# M_Board_2011.net
KiCad netlist of a schematic drawn in Altium Designer
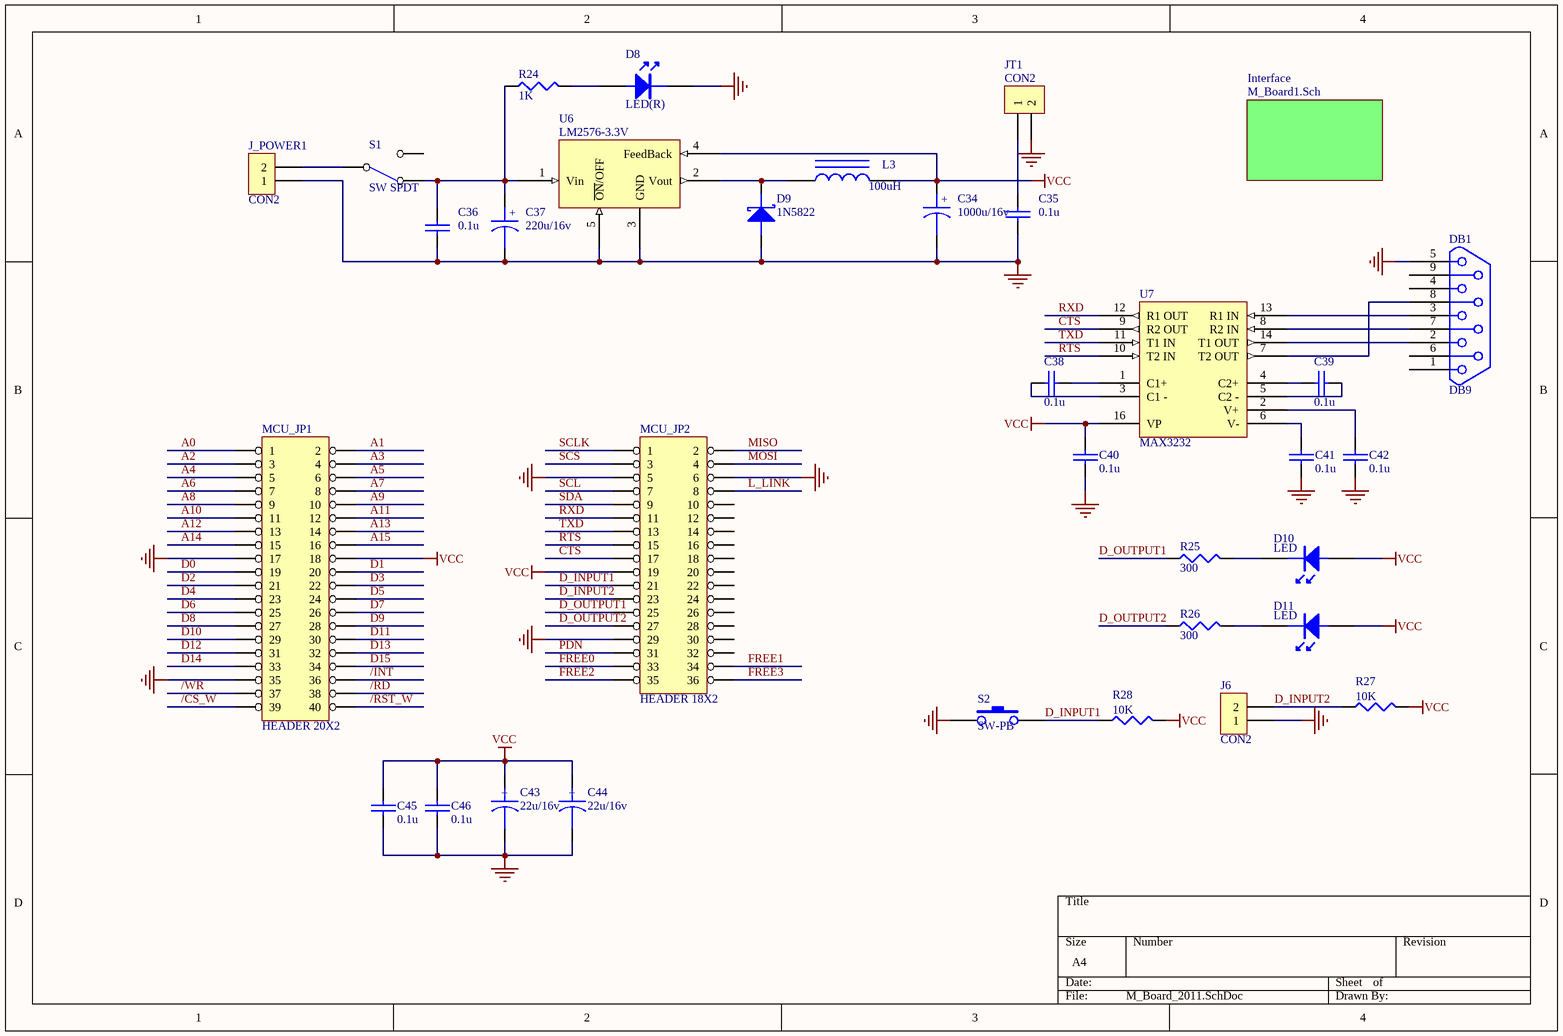
[diagram p0: M_Board_2011.SchDoc]

(export (version "E")
  (design (tool "Eeschema 10.0.6"))
  (components
    (comp (ref "C34")
      (value "1000u/16v")
      (footprint "RB.2/.4")
      (description "Capacitor")
      (libsource (lib "*") (part "CAPACITOR POL"))
    )
    (comp (ref "C35")
      (value "0.1u")
      (footprint "0603")
      (description "Capacitor")
      (libsource (lib "*") (part "CAP"))
    )
    (comp (ref "C36")
      (value "0.1u")
      (footprint "0603")
      (description "Capacitor")
      (libsource (lib "*") (part "CAP"))
    )
    (comp (ref "C37")
      (value "220u/16v")
      (footprint "RB.2/.4")
      (description "Capacitor")
      (libsource (lib "*") (part "CAPACITOR POL"))
    )
    (comp (ref "C38")
      (value "0.1u")
      (footprint "0603")
      (description "Capacitor")
      (libsource (lib "*") (part "CAP"))
    )
    (comp (ref "C39")
      (value "0.1u")
      (footprint "0603")
      (description "Capacitor")
      (libsource (lib "*") (part "CAP"))
    )
    (comp (ref "C40")
      (value "0.1u")
      (footprint "0603")
      (description "Capacitor")
      (libsource (lib "*") (part "CAP"))
    )
    (comp (ref "C41")
      (value "0.1u")
      (footprint "0603")
      (description "Capacitor")
      (libsource (lib "*") (part "CAP"))
    )
    (comp (ref "C42")
      (value "0.1u")
      (footprint "0603")
      (description "Capacitor")
      (libsource (lib "*") (part "CAP"))
    )
    (comp (ref "C43")
      (value "22u/16v")
      (footprint "RB.1/.2N")
      (description "Capacitor")
      (libsource (lib "") (part "CAPACITOR POL_1"))
    )
    (comp (ref "C44")
      (value "22u/16v")
      (footprint "RB.1/.2N")
      (description "Capacitor")
      (libsource (lib "") (part "CAPACITOR POL_1"))
    )
    (comp (ref "C45")
      (value "0.1u")
      (footprint "0603")
      (description "Capacitor")
      (libsource (lib "*") (part "CAP"))
    )
    (comp (ref "C46")
      (value "0.1u")
      (footprint "0603")
      (description "Capacitor")
      (libsource (lib "*") (part "CAP"))
    )
    (comp (ref "D8") (value "LED(R)") (footprint "LED2P") (libsource (lib "*") (part "LED")))
    (comp (ref "D9")
      (value "1N5822")
      (footprint "1005")
      (description "Schottky Diode")
      (libsource (lib "*") (part "DIODE SCHOTTKY"))
    )
    (comp (ref "D10") (value "LED") (footprint "LED2P") (libsource (lib "*") (part "LED")))
    (comp (ref "D11") (value "LED") (footprint "LED2P") (libsource (lib "*") (part "LED")))
    (comp (ref "DB1") (value "DB9") (footprint "DB9/F") (libsource (lib "*") (part "ICHIP3.S01_DB9_1")))
    (comp (ref "J6")
      (value "CON2")
      (footprint "SIP2")
      (description "Connector")
      (libsource (lib "*") (part "CON2"))
    )
    (comp (ref "JT1")
      (value "CON2")
      (footprint "SIP2")
      (description "Connector")
      (libsource (lib "") (part "CON2_1"))
    )
    (comp (ref "J_POWER1")
      (value "CON2")
      (footprint "PLUG")
      (description "Connector")
      (libsource (lib "*") (part "CON2"))
    )
    (comp (ref "L3") (value "100uH") (footprint "BED") (libsource (lib "*") (part "INDUCTOR IRON")))
    (comp (ref "MCU_JP1")
      (value "HEADER 20X2")
      (footprint "IDC40-2")
      (libsource (lib "*") (part "HEADER 20X2"))
    )
    (comp (ref "MCU_JP2")
      (value "HEADER 18X2")
      (footprint "IDC36-2")
      (libsource (lib "*") (part "HEADER 18X2"))
    )
    (comp (ref "R24") (value "1K") (footprint "0603") (libsource (lib "*") (part "RES1")))
    (comp (ref "R25") (value "300") (footprint "0603") (libsource (lib "*") (part "RES1")))
    (comp (ref "R26") (value "300") (footprint "0603") (libsource (lib "*") (part "RES1")))
    (comp (ref "R27") (value "10K") (footprint "0603") (libsource (lib "*") (part "RES1")))
    (comp (ref "R28") (value "10K") (footprint "0603") (libsource (lib "*") (part "RES1")))
    (comp (ref "S1") (value "SW SPDT") (footprint "SWITCH-3") (libsource (lib "*") (part "SW SPDT")))
    (comp (ref "S2") (value "SW-PB") (footprint "SW-4") (libsource (lib "*") (part "SW-PB")))
    (comp (ref "U6") (value "LM2576-3.3V") (footprint "DPAK-5") (libsource (lib "*") (part "LM2576")))
    (comp (ref "U7")
      (value "MAX3232")
      (footprint "SO-16")
      (description "+-15KV ESD-PROTECTED, +5V RS-232 TRANSCEIVERS")
      (libsource (lib "*") (part "MAX232ACPE(16)"))
    )
  )
  (nets
    (net (code "1") (name "/A0") (class "Default")
      (node (ref "MCU_JP1") (pin "1") (pinfunction "1_1") (pintype "passive"))
    )
    (net (code "2") (name "/A1") (class "Default")
      (node (ref "MCU_JP1") (pin "2") (pinfunction "2_2") (pintype "passive"))
    )
    (net (code "3") (name "/A2") (class "Default")
      (node (ref "MCU_JP1") (pin "3") (pinfunction "3_3") (pintype "passive"))
    )
    (net (code "4") (name "/A3") (class "Default")
      (node (ref "MCU_JP1") (pin "4") (pinfunction "4_4") (pintype "passive"))
    )
    (net (code "5") (name "/A4") (class "Default")
      (node (ref "MCU_JP1") (pin "5") (pinfunction "5_5") (pintype "passive"))
    )
    (net (code "6") (name "/A5") (class "Default")
      (node (ref "MCU_JP1") (pin "6") (pinfunction "6_6") (pintype "passive"))
    )
    (net (code "7") (name "/A6") (class "Default")
      (node (ref "MCU_JP1") (pin "7") (pinfunction "7_7") (pintype "passive"))
    )
    (net (code "8") (name "/A7") (class "Default")
      (node (ref "MCU_JP1") (pin "8") (pinfunction "8_8") (pintype "passive"))
    )
    (net (code "9") (name "/A8") (class "Default")
      (node (ref "MCU_JP1") (pin "9") (pinfunction "9_9") (pintype "passive"))
    )
    (net (code "10") (name "/A9") (class "Default")
      (node (ref "MCU_JP1") (pin "10") (pinfunction "10_10") (pintype "passive"))
    )
    (net (code "11") (name "/A10") (class "Default")
      (node (ref "MCU_JP1") (pin "11") (pinfunction "11_11") (pintype "passive"))
    )
    (net (code "12") (name "/A11") (class "Default")
      (node (ref "MCU_JP1") (pin "12") (pinfunction "12_12") (pintype "passive"))
    )
    (net (code "13") (name "/A12") (class "Default")
      (node (ref "MCU_JP1") (pin "13") (pinfunction "13_13") (pintype "passive"))
    )
    (net (code "14") (name "/A13") (class "Default")
      (node (ref "MCU_JP1") (pin "14") (pinfunction "14_14") (pintype "passive"))
    )
    (net (code "15") (name "/A14") (class "Default")
      (node (ref "MCU_JP1") (pin "15") (pinfunction "15_15") (pintype "passive"))
    )
    (net (code "16") (name "/A15") (class "Default")
      (node (ref "MCU_JP1") (pin "16") (pinfunction "16_16") (pintype "passive"))
    )
    (net (code "17") (name "/CTS") (class "Default")
      (node (ref "MCU_JP2") (pin "17") (pinfunction "17_17") (pintype "passive"))
      (node (ref "U7") (pin "9") (pinfunction "R2_OUT_9") (pintype "output"))
    )
    (net (code "18") (name "/D0") (class "Default")
      (node (ref "MCU_JP1") (pin "19") (pinfunction "19_19") (pintype "passive"))
    )
    (net (code "19") (name "/D1") (class "Default")
      (node (ref "MCU_JP1") (pin "20") (pinfunction "20_20") (pintype "passive"))
    )
    (net (code "20") (name "/D2") (class "Default")
      (node (ref "MCU_JP1") (pin "21") (pinfunction "21_21") (pintype "passive"))
    )
    (net (code "21") (name "/D3") (class "Default")
      (node (ref "MCU_JP1") (pin "22") (pinfunction "22_22") (pintype "passive"))
    )
    (net (code "22") (name "/D4") (class "Default")
      (node (ref "MCU_JP1") (pin "23") (pinfunction "23_23") (pintype "passive"))
    )
    (net (code "23") (name "/D5") (class "Default")
      (node (ref "MCU_JP1") (pin "24") (pinfunction "24_24") (pintype "passive"))
    )
    (net (code "24") (name "/D6") (class "Default")
      (node (ref "MCU_JP1") (pin "25") (pinfunction "25_25") (pintype "passive"))
    )
    (net (code "25") (name "/D7") (class "Default")
      (node (ref "MCU_JP1") (pin "26") (pinfunction "26_26") (pintype "passive"))
    )
    (net (code "26") (name "/D8") (class "Default")
      (node (ref "MCU_JP1") (pin "27") (pinfunction "27_27") (pintype "passive"))
    )
    (net (code "27") (name "/D9") (class "Default")
      (node (ref "MCU_JP1") (pin "28") (pinfunction "28_28") (pintype "passive"))
    )
    (net (code "28") (name "/D10") (class "Default")
      (node (ref "MCU_JP1") (pin "29") (pinfunction "29_29") (pintype "passive"))
    )
    (net (code "29") (name "/D11") (class "Default")
      (node (ref "MCU_JP1") (pin "30") (pinfunction "30_30") (pintype "passive"))
    )
    (net (code "30") (name "/D12") (class "Default")
      (node (ref "MCU_JP1") (pin "31") (pinfunction "31_31") (pintype "passive"))
    )
    (net (code "31") (name "/D13") (class "Default")
      (node (ref "MCU_JP1") (pin "32") (pinfunction "32_32") (pintype "passive"))
    )
    (net (code "32") (name "/D14") (class "Default")
      (node (ref "MCU_JP1") (pin "33") (pinfunction "33_33") (pintype "passive"))
    )
    (net (code "33") (name "/D15") (class "Default")
      (node (ref "MCU_JP1") (pin "34") (pinfunction "34_34") (pintype "passive"))
    )
    (net (code "34") (name "/D_INPUT1") (class "Default")
      (node (ref "MCU_JP2") (pin "21") (pinfunction "21_21") (pintype "passive"))
      (node (ref "R28") (pin "1") (pinfunction "1_1") (pintype "passive"))
      (node (ref "S2") (pin "2") (pinfunction "2_2") (pintype "passive"))
    )
    (net (code "35") (name "/D_INPUT2") (class "Default")
      (node (ref "J6") (pin "2") (pinfunction "2_2") (pintype "passive"))
      (node (ref "MCU_JP2") (pin "23") (pinfunction "23_23") (pintype "passive"))
      (node (ref "R27") (pin "1") (pinfunction "1_1") (pintype "passive"))
    )
    (net (code "36") (name "/D_OUTPUT1") (class "Default")
      (node (ref "MCU_JP2") (pin "25") (pinfunction "25_25") (pintype "passive"))
      (node (ref "R25") (pin "1") (pinfunction "1_1") (pintype "passive"))
    )
    (net (code "37") (name "/D_OUTPUT2") (class "Default")
      (node (ref "MCU_JP2") (pin "27") (pinfunction "27_27") (pintype "passive"))
      (node (ref "R26") (pin "1") (pinfunction "1_1") (pintype "passive"))
    )
    (net (code "38") (name "/FREE0") (class "Default")
      (node (ref "MCU_JP2") (pin "33") (pinfunction "33_33") (pintype "passive"))
    )
    (net (code "39") (name "/FREE1") (class "Default")
      (node (ref "MCU_JP2") (pin "34") (pinfunction "34_34") (pintype "passive"))
    )
    (net (code "40") (name "/FREE2") (class "Default")
      (node (ref "MCU_JP2") (pin "35") (pinfunction "35_35") (pintype "passive"))
    )
    (net (code "41") (name "/FREE3") (class "Default")
      (node (ref "MCU_JP2") (pin "36") (pinfunction "36_36") (pintype "passive"))
    )
    (net (code "42") (name "/L_LINK") (class "Default")
      (node (ref "MCU_JP2") (pin "8") (pinfunction "8_8") (pintype "passive"))
    )
    (net (code "43") (name "/MISO") (class "Default")
      (node (ref "MCU_JP2") (pin "2") (pinfunction "2_2") (pintype "passive"))
    )
    (net (code "44") (name "/MOSI") (class "Default")
      (node (ref "MCU_JP2") (pin "4") (pinfunction "4_4") (pintype "passive"))
    )
    (net (code "45") (name "/PDN") (class "Default")
      (node (ref "MCU_JP2") (pin "31") (pinfunction "31_31") (pintype "passive"))
    )
    (net (code "46") (name "/RTS") (class "Default")
      (node (ref "MCU_JP2") (pin "15") (pinfunction "15_15") (pintype "passive"))
      (node (ref "U7") (pin "10") (pinfunction "T2_IN_10") (pintype "input"))
    )
    (net (code "47") (name "/RXD") (class "Default")
      (node (ref "MCU_JP2") (pin "11") (pinfunction "11_11") (pintype "passive"))
      (node (ref "U7") (pin "12") (pinfunction "R1_OUT_12") (pintype "output"))
    )
    (net (code "48") (name "/SCL") (class "Default")
      (node (ref "MCU_JP2") (pin "7") (pinfunction "7_7") (pintype "passive"))
    )
    (net (code "49") (name "/SCLK") (class "Default")
      (node (ref "MCU_JP2") (pin "1") (pinfunction "1_1") (pintype "passive"))
    )
    (net (code "50") (name "/SCS") (class "Default")
      (node (ref "MCU_JP2") (pin "3") (pinfunction "3_3") (pintype "passive"))
    )
    (net (code "51") (name "/SDA") (class "Default")
      (node (ref "MCU_JP2") (pin "9") (pinfunction "9_9") (pintype "passive"))
    )
    (net (code "52") (name "/TXD") (class "Default")
      (node (ref "MCU_JP2") (pin "13") (pinfunction "13_13") (pintype "passive"))
      (node (ref "U7") (pin "11") (pinfunction "T1_IN_11") (pintype "input"))
    )
    (net (code "53") (name "/{slash}CS_W") (class "Default")
      (node (ref "MCU_JP1") (pin "39") (pinfunction "39_39") (pintype "passive"))
    )
    (net (code "54") (name "/{slash}INT") (class "Default")
      (node (ref "MCU_JP1") (pin "36") (pinfunction "36_36") (pintype "passive"))
    )
    (net (code "55") (name "/{slash}RD") (class "Default")
      (node (ref "MCU_JP1") (pin "38") (pinfunction "38_38") (pintype "passive"))
    )
    (net (code "56") (name "/{slash}RST_W") (class "Default")
      (node (ref "MCU_JP1") (pin "40") (pinfunction "40_40") (pintype "passive"))
    )
    (net (code "57") (name "/{slash}WR") (class "Default")
      (node (ref "MCU_JP1") (pin "37") (pinfunction "37_37") (pintype "passive"))
    )
    (net (code "58") (name "GND") (class "Default")
      (node (ref "C34") (pin "2") (pinfunction "2_2") (pintype "passive"))
      (node (ref "C35") (pin "2") (pinfunction "2_2") (pintype "passive"))
      (node (ref "C36") (pin "2") (pinfunction "2_2") (pintype "passive"))
      (node (ref "C37") (pin "2") (pinfunction "2_2") (pintype "passive"))
      (node (ref "C40") (pin "2") (pinfunction "2_2") (pintype "passive"))
      (node (ref "C41") (pin "2") (pinfunction "2_2") (pintype "passive"))
      (node (ref "C42") (pin "2") (pinfunction "2_2") (pintype "passive"))
      (node (ref "C43") (pin "2") (pinfunction "2_2") (pintype "passive"))
      (node (ref "C44") (pin "2") (pinfunction "2_2") (pintype "passive"))
      (node (ref "C45") (pin "1") (pinfunction "1_1") (pintype "passive"))
      (node (ref "C46") (pin "1") (pinfunction "1_1") (pintype "passive"))
      (node (ref "D8") (pin "K") (pinfunction "2_K") (pintype "passive"))
      (node (ref "D9") (pin "1") (pinfunction "A_1") (pintype "passive"))
      (node (ref "DB1") (pin "5") (pintype "passive"))
      (node (ref "J6") (pin "1") (pinfunction "1_1") (pintype "passive"))
      (node (ref "JT1") (pin "2") (pinfunction "2_2") (pintype "passive"))
      (node (ref "J_POWER1") (pin "1") (pinfunction "1_1") (pintype "passive"))
      (node (ref "MCU_JP1") (pin "17") (pinfunction "17_17") (pintype "passive"))
      (node (ref "MCU_JP1") (pin "35") (pinfunction "35_35") (pintype "passive"))
      (node (ref "MCU_JP2") (pin "29") (pinfunction "29_29") (pintype "passive"))
      (node (ref "MCU_JP2") (pin "5") (pinfunction "5_5") (pintype "passive"))
      (node (ref "MCU_JP2") (pin "6") (pinfunction "6_6") (pintype "passive"))
      (node (ref "S2") (pin "1") (pinfunction "1_1") (pintype "passive"))
      (node (ref "U6") (pin "3") (pinfunction "GND_3") (pintype "power_in"))
      (node (ref "U6") (pin "5") (pinfunction "~{ON}/OFF_5") (pintype "input"))
      (node (ref "U7") (pin "15") (pinfunction "GND_15") (pintype "power_in"))
    )
    (net (code "59") (name "Net-(C35-Pad1)") (class "Default")
      (node (ref "C35") (pin "1") (pinfunction "1_1") (pintype "passive"))
      (node (ref "JT1") (pin "1") (pinfunction "1_1") (pintype "passive"))
    )
    (net (code "60") (name "Net-(D8-1)") (class "Default")
      (node (ref "D8") (pin "A") (pinfunction "1_A") (pintype "passive"))
      (node (ref "R24") (pin "2") (pinfunction "2_2") (pintype "passive"))
    )
    (net (code "61") (name "Net-(D9-K)") (class "Default")
      (node (ref "D9") (pin "2") (pinfunction "K_2") (pintype "passive"))
      (node (ref "L3") (pin "1") (pinfunction "1_1") (pintype "passive"))
      (node (ref "U6") (pin "2") (pinfunction "Vout_2") (pintype "output"))
    )
    (net (code "62") (name "Net-(D10-2)") (class "Default")
      (node (ref "D10") (pin "K") (pinfunction "2_K") (pintype "passive"))
      (node (ref "R25") (pin "2") (pinfunction "2_2") (pintype "passive"))
    )
    (net (code "63") (name "Net-(D11-2)") (class "Default")
      (node (ref "D11") (pin "K") (pinfunction "2_K") (pintype "passive"))
      (node (ref "R26") (pin "2") (pinfunction "2_2") (pintype "passive"))
    )
    (net (code "64") (name "Net-(S1-COMMON)") (class "Default")
      (node (ref "J_POWER1") (pin "2") (pinfunction "2_2") (pintype "passive"))
      (node (ref "S1") (pin "1") (pinfunction "COMMON_1") (pintype "passive"))
    )
    (net (code "65") (name "Net-(S1-NC)") (class "Default")
      (node (ref "C36") (pin "1") (pinfunction "1_1") (pintype "passive"))
      (node (ref "C37") (pin "1") (pinfunction "1_1") (pintype "passive"))
      (node (ref "R24") (pin "1") (pinfunction "1_1") (pintype "passive"))
      (node (ref "S1") (pin "2") (pinfunction "NC_2") (pintype "passive"))
      (node (ref "U6") (pin "1") (pinfunction "Vin_1") (pintype "input"))
    )
    (net (code "66") (name "Net-(U7-C1+)") (class "Default")
      (node (ref "C38") (pin "2") (pinfunction "2_2") (pintype "passive"))
      (node (ref "U7") (pin "1") (pinfunction "C1+_1") (pintype "passive"))
    )
    (net (code "67") (name "Net-(U7-C1_-)") (class "Default")
      (node (ref "C38") (pin "1") (pinfunction "1_1") (pintype "passive"))
      (node (ref "U7") (pin "3") (pinfunction "C1_-_3") (pintype "passive"))
    )
    (net (code "68") (name "Net-(U7-C2+)") (class "Default")
      (node (ref "C39") (pin "1") (pinfunction "1_1") (pintype "passive"))
      (node (ref "U7") (pin "4") (pinfunction "C2+_4") (pintype "passive"))
    )
    (net (code "69") (name "Net-(U7-C2_-)") (class "Default")
      (node (ref "C39") (pin "2") (pinfunction "2_2") (pintype "passive"))
      (node (ref "U7") (pin "5") (pinfunction "C2_-_5") (pintype "passive"))
    )
    (net (code "70") (name "Net-(U7-R1_IN)") (class "Default")
      (node (ref "DB1") (pin "3") (pintype "passive"))
      (node (ref "U7") (pin "13") (pinfunction "R1_IN_13") (pintype "input"))
    )
    (net (code "71") (name "Net-(U7-R2_IN)") (class "Default")
      (node (ref "DB1") (pin "7") (pintype "passive"))
      (node (ref "U7") (pin "8") (pinfunction "R2_IN_8") (pintype "input"))
    )
    (net (code "72") (name "Net-(U7-T1_OUT)") (class "Default")
      (node (ref "DB1") (pin "2") (pintype "passive"))
      (node (ref "U7") (pin "14") (pinfunction "T1_OUT_14") (pintype "output"))
    )
    (net (code "73") (name "Net-(U7-T2_OUT)") (class "Default")
      (node (ref "DB1") (pin "8") (pintype "passive"))
      (node (ref "U7") (pin "7") (pinfunction "T2_OUT_7") (pintype "output"))
    )
    (net (code "74") (name "Net-(U7-V+)") (class "Default")
      (node (ref "C42") (pin "1") (pinfunction "1_1") (pintype "passive"))
      (node (ref "U7") (pin "2") (pinfunction "V+_2") (pintype "power_in"))
    )
    (net (code "75") (name "Net-(U7-V-)") (class "Default")
      (node (ref "C41") (pin "1") (pinfunction "1_1") (pintype "passive"))
      (node (ref "U7") (pin "6") (pinfunction "V-_6") (pintype "power_in"))
    )
    (net (code "76") (name "VCC") (class "Default")
      (node (ref "C34") (pin "1") (pinfunction "1_1") (pintype "passive"))
      (node (ref "C40") (pin "1") (pinfunction "1_1") (pintype "passive"))
      (node (ref "C43") (pin "1") (pinfunction "1_1") (pintype "passive"))
      (node (ref "C44") (pin "1") (pinfunction "1_1") (pintype "passive"))
      (node (ref "C45") (pin "2") (pinfunction "2_2") (pintype "passive"))
      (node (ref "C46") (pin "2") (pinfunction "2_2") (pintype "passive"))
      (node (ref "D10") (pin "A") (pinfunction "1_A") (pintype "passive"))
      (node (ref "D11") (pin "A") (pinfunction "1_A") (pintype "passive"))
      (node (ref "L3") (pin "2") (pinfunction "2_2") (pintype "passive"))
      (node (ref "MCU_JP1") (pin "18") (pinfunction "18_18") (pintype "passive"))
      (node (ref "MCU_JP2") (pin "19") (pinfunction "19_19") (pintype "passive"))
      (node (ref "R27") (pin "2") (pinfunction "2_2") (pintype "passive"))
      (node (ref "R28") (pin "2") (pinfunction "2_2") (pintype "passive"))
      (node (ref "U6") (pin "4") (pinfunction "FeedBack_4") (pintype "input"))
      (node (ref "U7") (pin "16") (pinfunction "VP_16") (pintype "power_in"))
    )
    (net (code "77") (name "unconnected-(DB1-Pad1)") (class "Default")
      (node (ref "DB1") (pin "1") (pintype "passive"))
    )
    (net (code "78") (name "unconnected-(DB1-Pad4)") (class "Default")
      (node (ref "DB1") (pin "4") (pintype "passive"))
    )
    (net (code "79") (name "unconnected-(DB1-Pad6)") (class "Default")
      (node (ref "DB1") (pin "6") (pintype "passive"))
    )
    (net (code "80") (name "unconnected-(DB1-Pad9)") (class "Default")
      (node (ref "DB1") (pin "9") (pintype "passive"))
    )
    (net (code "81") (name "unconnected-(MCU_JP2-Pad10)") (class "Default")
      (node (ref "MCU_JP2") (pin "10") (pinfunction "10_10") (pintype "passive"))
    )
    (net (code "82") (name "unconnected-(MCU_JP2-Pad12)") (class "Default")
      (node (ref "MCU_JP2") (pin "12") (pinfunction "12_12") (pintype "passive"))
    )
    (net (code "83") (name "unconnected-(MCU_JP2-Pad14)") (class "Default")
      (node (ref "MCU_JP2") (pin "14") (pinfunction "14_14") (pintype "passive"))
    )
    (net (code "84") (name "unconnected-(MCU_JP2-Pad16)") (class "Default")
      (node (ref "MCU_JP2") (pin "16") (pinfunction "16_16") (pintype "passive"))
    )
    (net (code "85") (name "unconnected-(MCU_JP2-Pad18)") (class "Default")
      (node (ref "MCU_JP2") (pin "18") (pinfunction "18_18") (pintype "passive"))
    )
    (net (code "86") (name "unconnected-(MCU_JP2-Pad20)") (class "Default")
      (node (ref "MCU_JP2") (pin "20") (pinfunction "20_20") (pintype "passive"))
    )
    (net (code "87") (name "unconnected-(MCU_JP2-Pad22)") (class "Default")
      (node (ref "MCU_JP2") (pin "22") (pinfunction "22_22") (pintype "passive"))
    )
    (net (code "88") (name "unconnected-(MCU_JP2-Pad24)") (class "Default")
      (node (ref "MCU_JP2") (pin "24") (pinfunction "24_24") (pintype "passive"))
    )
    (net (code "89") (name "unconnected-(MCU_JP2-Pad26)") (class "Default")
      (node (ref "MCU_JP2") (pin "26") (pinfunction "26_26") (pintype "passive"))
    )
    (net (code "90") (name "unconnected-(MCU_JP2-Pad28)") (class "Default")
      (node (ref "MCU_JP2") (pin "28") (pinfunction "28_28") (pintype "passive"))
    )
    (net (code "91") (name "unconnected-(MCU_JP2-Pad30)") (class "Default")
      (node (ref "MCU_JP2") (pin "30") (pinfunction "30_30") (pintype "passive"))
    )
    (net (code "92") (name "unconnected-(MCU_JP2-Pad32)") (class "Default")
      (node (ref "MCU_JP2") (pin "32") (pinfunction "32_32") (pintype "passive"))
    )
    (net (code "93") (name "unconnected-(S1-NO-Pad3)") (class "Default")
      (node (ref "S1") (pin "3") (pinfunction "NO_3") (pintype "passive"))
    )
  )
)
